# BMS_LOST_V1.net
KiCad netlist of a schematic drawn in Altium Designer
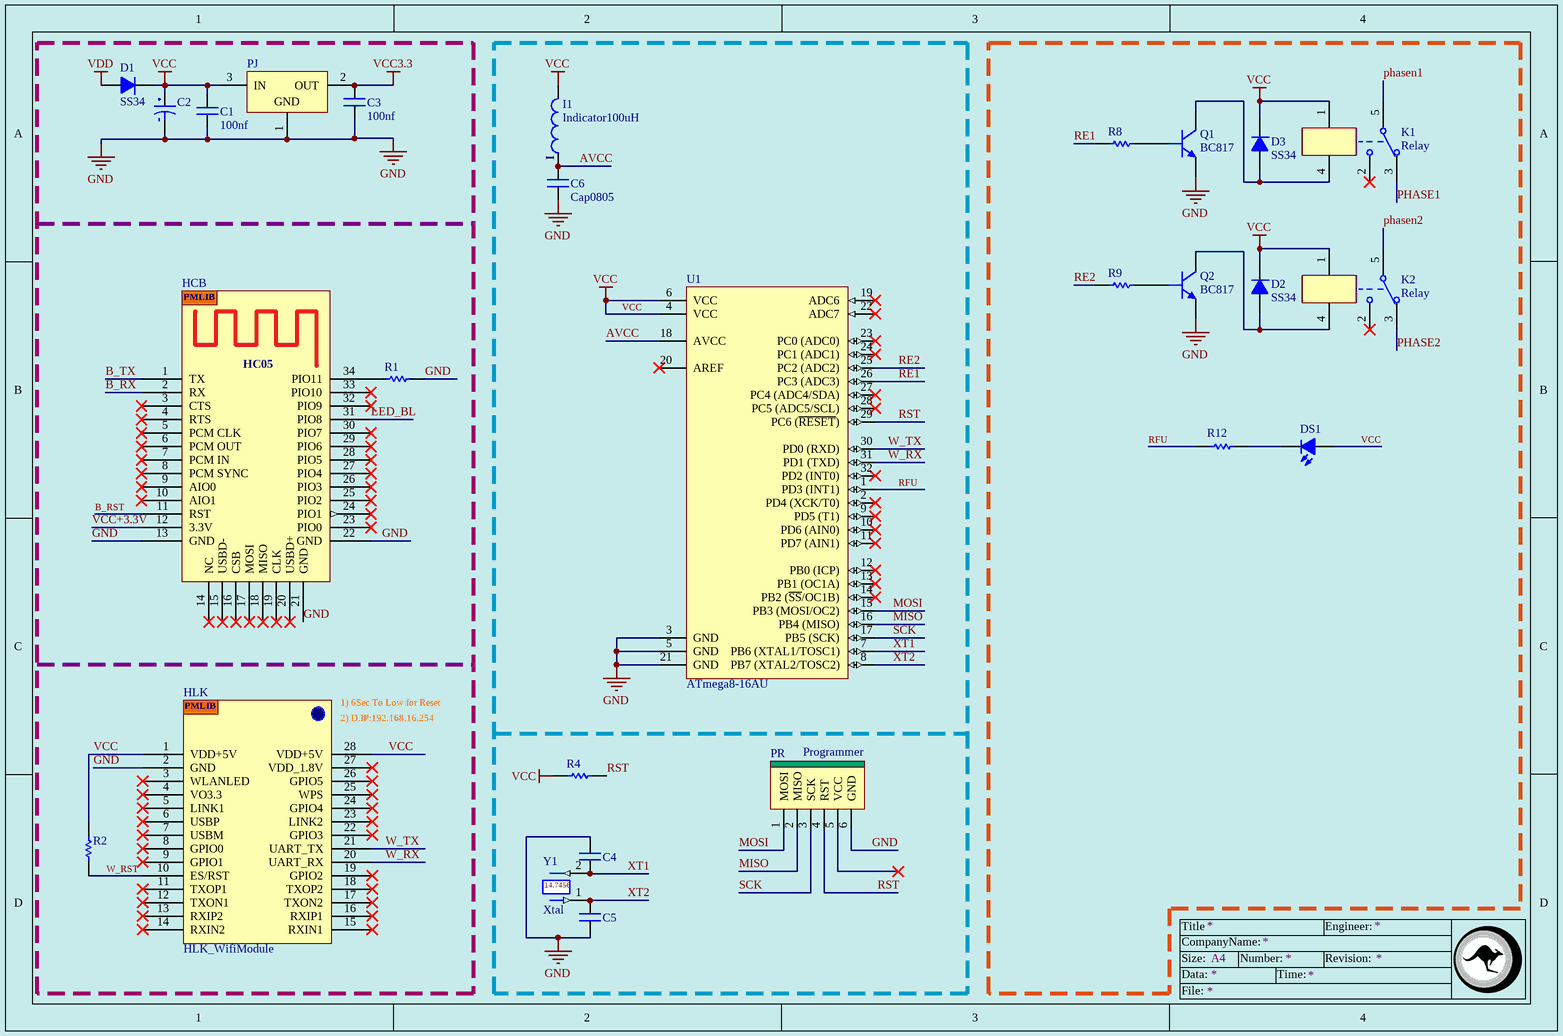
[diagram p0: BMS_LOST_V1.SchDoc]

(export (version "E")
  (design (tool "Eeschema 10.0.6"))
  (components
    (comp (ref "C1")
      (value "100nf")
      (footprint "Cap0805")
      (description "surface mount capacitor (size 805)")
      (libsource (lib "PMLIB") (part "Cap0805"))
    )
    (comp (ref "C2") (value "Cap_4mm") (footprint "2220") (libsource (lib "PMLIB") (part "Cap_Pola")))
    (comp (ref "C3")
      (value "100nf")
      (footprint "Cap0805")
      (description "surface mount capacitor (size 805)")
      (libsource (lib "PMLIB") (part "Cap0805"))
    )
    (comp (ref "C4")
      (value "CAP 805")
      (footprint "Cap0805")
      (description "surface mount capacitor (size 805)")
      (libsource (lib "PMLIB") (part "Cap0805"))
    )
    (comp (ref "C5")
      (value "CAP 805")
      (footprint "Cap0805")
      (description "surface mount capacitor (size 805)")
      (libsource (lib "PMLIB") (part "Cap0805"))
    )
    (comp (ref "C6")
      (value "Cap0805")
      (footprint "Cap0805")
      (description "surface mount capacitor (size 805)")
      (libsource (lib "PMLIB") (part "Cap0805"))
    )
    (comp (ref "D1") (value "SS34") (footprint "Diod-1A-SMD") (libsource (lib "PMLIB") (part "Diode")))
    (comp (ref "D2") (value "SS34") (footprint "Diod-1A-SMD") (libsource (lib "PMLIB") (part "Diode")))
    (comp (ref "D3") (value "SS34") (footprint "Diod-1A-SMD") (libsource (lib "PMLIB") (part "Diode")))
    (comp (ref "DS1") (value "LED1") (footprint "LED3MM") (libsource (lib "PMLIB") (part "LED1")))
    (comp (ref "HC")
      (value "HC05_Bluetooth")
      (footprint "HC05_Bluetooth")
      (libsource (lib "PMLIB") (part "HC05_Bluetooth"))
    )
    (comp (ref "HLK")
      (value "HLK_WifiModule")
      (footprint "HLK")
      (libsource (lib "PMLIB") (part "HLK_WifiModule"))
    )
    (comp (ref "I1")
      (value "Indicator100uH")
      (footprint "Indicator0805")
      (libsource (lib "PMLIB") (part "Indicator100uH"))
    )
    (comp (ref "K1")
      (value "Relay")
      (footprint "RelayMilionMiniS-Z")
      (libsource (lib "PMLIB") (part "RelayMilon"))
    )
    (comp (ref "K2")
      (value "Relay")
      (footprint "RelayMilionMiniS-Z")
      (libsource (lib "PMLIB") (part "RelayMilon"))
    )
    (comp (ref "PJ")
      (value "PJ1117_3.3V")
      (footprint "PJ1117s")
      (libsource (lib "PMLIB") (part "PJ1117_3.3V"))
    )
    (comp (ref "PR")
      (value "Programmer")
      (footprint "Programmer")
      (libsource (lib "PMLIB") (part "Programmer"))
    )
    (comp (ref "Q1") (value "BC817") (footprint "SOT23") (libsource (lib "PMLIB") (part "Transistor NPN")))
    (comp (ref "Q2") (value "BC817") (footprint "SOT23") (libsource (lib "PMLIB") (part "Transistor NPN")))
    (comp (ref "R1") (value "Res 0805") (footprint "R0805") (libsource (lib "PMLIB") (part "Res 0805")))
    (comp (ref "R2") (value "Res 0805") (footprint "R0805") (libsource (lib "PMLIB") (part "Res 0805")))
    (comp (ref "R4") (value "Res 0805") (footprint "R0805") (libsource (lib "PMLIB") (part "Res 0805")))
    (comp (ref "R8") (value "Res 0805") (footprint "R0805") (libsource (lib "PMLIB") (part "Res 0805")))
    (comp (ref "R9") (value "Res 0805") (footprint "R0805") (libsource (lib "PMLIB") (part "Res 0805")))
    (comp (ref "R12") (value "330") (footprint "R0805") (libsource (lib "PMLIB") (part "Res 0805")))
    (comp (ref "U1")
      (value "ATmega8-16AU")
      (footprint "32A_N")
      (libsource (lib "Atmel Microcontroller megaAVR") (part "ATmega8-16AU"))
    )
    (comp (ref "Y1") (value "Xtal") (footprint "CrystallB") (libsource (lib "PMLIB") (part "Crystal")))
  )
  (nets
    (net (code "1") (name "/AVCC") (class "Default")
      (node (ref "C6") (pin "2") (pinfunction "2_2") (pintype "passive"))
      (node (ref "I1") (pin "1") (pinfunction "1_1") (pintype "passive"))
      (node (ref "U1") (pin "18") (pinfunction "AVCC_18") (pintype "power_in"))
    )
    (net (code "2") (name "/B_RST") (class "Default")
      (node (ref "HC") (pin "11") (pinfunction "RST_11") (pintype "passive"))
    )
    (net (code "3") (name "/B_RX") (class "Default")
      (node (ref "HC") (pin "2") (pinfunction "RX_2") (pintype "passive"))
    )
    (net (code "4") (name "/B_TX") (class "Default")
      (node (ref "HC") (pin "1") (pinfunction "TX_1") (pintype "passive"))
    )
    (net (code "5") (name "/LED_BL") (class "Default")
      (node (ref "HC") (pin "31") (pinfunction "PIO8_31") (pintype "passive"))
    )
    (net (code "6") (name "/MISO") (class "Default")
      (node (ref "PR") (pin "2") (pinfunction "MISO_2") (pintype "passive"))
      (node (ref "U1") (pin "16") (pinfunction "PB4_(MISO)_16") (pintype "bidirectional"))
    )
    (net (code "7") (name "/MOSI") (class "Default")
      (node (ref "PR") (pin "1") (pinfunction "MOSI_1") (pintype "passive"))
      (node (ref "U1") (pin "15") (pinfunction "PB3_(MOSI/OC2)_15") (pintype "bidirectional"))
    )
    (net (code "8") (name "/PHASE1") (class "Default")
      (node (ref "K1") (pin "3") (pinfunction "3_3") (pintype "passive"))
    )
    (net (code "9") (name "/PHASE2") (class "Default")
      (node (ref "K2") (pin "3") (pinfunction "3_3") (pintype "passive"))
    )
    (net (code "10") (name "/RE1") (class "Default")
      (node (ref "R8") (pin "2") (pinfunction "2_2") (pintype "passive"))
      (node (ref "U1") (pin "26") (pinfunction "PC3_(ADC3)_26") (pintype "bidirectional"))
    )
    (net (code "11") (name "/RE2") (class "Default")
      (node (ref "R9") (pin "2") (pinfunction "2_2") (pintype "passive"))
      (node (ref "U1") (pin "25") (pinfunction "PC2_(ADC2)_25") (pintype "bidirectional"))
    )
    (net (code "12") (name "/RFU") (class "Default")
      (node (ref "R12") (pin "2") (pinfunction "2_2") (pintype "passive"))
      (node (ref "U1") (pin "1") (pinfunction "PD3_(INT1)_1") (pintype "bidirectional"))
    )
    (net (code "13") (name "/RST") (class "Default")
      (node (ref "PR") (pin "4") (pinfunction "RST_4") (pintype "passive"))
      (node (ref "R4") (pin "1") (pinfunction "1_1") (pintype "passive"))
      (node (ref "U1") (pin "29") (pinfunction "PC6_(~{RESET})_29") (pintype "bidirectional"))
    )
    (net (code "14") (name "/SCK") (class "Default")
      (node (ref "PR") (pin "3") (pinfunction "SCK_3") (pintype "passive"))
      (node (ref "U1") (pin "17") (pinfunction "PB5_(SCK)_17") (pintype "bidirectional"))
    )
    (net (code "15") (name "/VCC+3.3V") (class "Default")
      (node (ref "HC") (pin "12") (pinfunction "3.3V_12") (pintype "passive"))
    )
    (net (code "16") (name "/W_RST") (class "Default")
      (node (ref "HLK") (pin "10") (pinfunction "ES/RST_10") (pintype "passive"))
      (node (ref "R2") (pin "2") (pinfunction "2_2") (pintype "passive"))
    )
    (net (code "17") (name "/W_RX") (class "Default")
      (node (ref "HLK") (pin "20") (pinfunction "UART_RX_20") (pintype "passive"))
      (node (ref "U1") (pin "31") (pinfunction "PD1_(TXD)_31") (pintype "bidirectional"))
    )
    (net (code "18") (name "/W_TX") (class "Default")
      (node (ref "HLK") (pin "21") (pinfunction "UART_TX_21") (pintype "passive"))
      (node (ref "U1") (pin "30") (pinfunction "PD0_(RXD)_30") (pintype "bidirectional"))
    )
    (net (code "19") (name "/XT1") (class "Default")
      (node (ref "C4") (pin "1") (pinfunction "1_1") (pintype "passive"))
      (node (ref "U1") (pin "7") (pinfunction "PB6_(XTAL1/TOSC1)_7") (pintype "bidirectional"))
      (node (ref "Y1") (pin "2") (pinfunction "2_2") (pintype "input"))
    )
    (net (code "20") (name "/XT2") (class "Default")
      (node (ref "C5") (pin "2") (pinfunction "2_2") (pintype "passive"))
      (node (ref "U1") (pin "8") (pinfunction "PB7_(XTAL2/TOSC2)_8") (pintype "bidirectional"))
      (node (ref "Y1") (pin "1") (pinfunction "1_1") (pintype "output"))
    )
    (net (code "21") (name "/phasen1") (class "Default")
      (node (ref "K1") (pin "5") (pinfunction "5_5") (pintype "passive"))
    )
    (net (code "22") (name "/phasen2") (class "Default")
      (node (ref "K2") (pin "5") (pinfunction "5_5") (pintype "passive"))
    )
    (net (code "23") (name "GND") (class "Default")
      (node (ref "C1") (pin "2") (pinfunction "2_2") (pintype "passive"))
      (node (ref "C2") (pin "1") (pinfunction "1_1") (pintype "passive"))
      (node (ref "C3") (pin "2") (pinfunction "2_2") (pintype "passive"))
      (node (ref "C4") (pin "2") (pinfunction "2_2") (pintype "passive"))
      (node (ref "C5") (pin "1") (pinfunction "1_1") (pintype "passive"))
      (node (ref "C6") (pin "1") (pinfunction "1_1") (pintype "passive"))
      (node (ref "HC") (pin "13") (pinfunction "GND_13") (pintype "power_in"))
      (node (ref "HC") (pin "21") (pinfunction "GND_21") (pintype "passive"))
      (node (ref "HC") (pin "22") (pinfunction "GND_22") (pintype "passive"))
      (node (ref "HLK") (pin "2") (pinfunction "GND_2") (pintype "passive"))
      (node (ref "PJ") (pin "1") (pinfunction "GND_1") (pintype "power_in"))
      (node (ref "PR") (pin "6") (pinfunction "GND_6") (pintype "passive"))
      (node (ref "Q1") (pin "2") (pinfunction "E_2") (pintype "passive"))
      (node (ref "Q2") (pin "2") (pinfunction "E_2") (pintype "passive"))
      (node (ref "R1") (pin "1") (pinfunction "1_1") (pintype "passive"))
      (node (ref "U1") (pin "21") (pinfunction "GND_21") (pintype "power_in"))
      (node (ref "U1") (pin "3") (pinfunction "GND_3") (pintype "power_in"))
      (node (ref "U1") (pin "5") (pinfunction "GND_5") (pintype "power_in"))
    )
    (net (code "24") (name "Net-(DS1-PadK)") (class "Default")
      (node (ref "DS1") (pin "K") (pinfunction "K_K") (pintype "passive"))
      (node (ref "R12") (pin "1") (pinfunction "1_1") (pintype "passive"))
    )
    (net (code "25") (name "Net-(HCB-PIO11)") (class "Default")
      (node (ref "HC") (pin "34") (pinfunction "PIO11_34") (pintype "passive"))
      (node (ref "R1") (pin "2") (pinfunction "2_2") (pintype "passive"))
    )
    (net (code "26") (name "Net-(Q1-B)") (class "Default")
      (node (ref "Q1") (pin "1") (pinfunction "B_1") (pintype "passive"))
      (node (ref "R8") (pin "1") (pinfunction "1_1") (pintype "passive"))
    )
    (net (code "27") (name "Net-(Q1-C)") (class "Default")
      (node (ref "D3") (pin "A") (pinfunction "A_A") (pintype "passive"))
      (node (ref "K1") (pin "4") (pinfunction "4_4") (pintype "passive"))
      (node (ref "Q1") (pin "3") (pinfunction "C_3") (pintype "passive"))
    )
    (net (code "28") (name "Net-(Q2-B)") (class "Default")
      (node (ref "Q2") (pin "1") (pinfunction "B_1") (pintype "passive"))
      (node (ref "R9") (pin "1") (pinfunction "1_1") (pintype "passive"))
    )
    (net (code "29") (name "Net-(Q2-C)") (class "Default")
      (node (ref "D2") (pin "A") (pinfunction "A_A") (pintype "passive"))
      (node (ref "K2") (pin "4") (pinfunction "4_4") (pintype "passive"))
      (node (ref "Q2") (pin "3") (pinfunction "C_3") (pintype "passive"))
    )
    (net (code "30") (name "VCC") (class "Default")
      (node (ref "C1") (pin "1") (pinfunction "1_1") (pintype "passive"))
      (node (ref "C2") (pin "2") (pinfunction "2_2") (pintype "passive"))
      (node (ref "D1") (pin "K") (pinfunction "K_K") (pintype "passive"))
      (node (ref "D2") (pin "K") (pinfunction "K_K") (pintype "passive"))
      (node (ref "D3") (pin "K") (pinfunction "K_K") (pintype "passive"))
      (node (ref "DS1") (pin "A") (pinfunction "A_A") (pintype "passive"))
      (node (ref "HLK") (pin "1") (pinfunction "VDD+5V_1") (pintype "passive"))
      (node (ref "HLK") (pin "28") (pinfunction "VDD+5V_28") (pintype "passive"))
      (node (ref "I1") (pin "2") (pinfunction "2_2") (pintype "passive"))
      (node (ref "K1") (pin "1") (pinfunction "1_1") (pintype "passive"))
      (node (ref "K2") (pin "1") (pinfunction "1_1") (pintype "passive"))
      (node (ref "PJ") (pin "3") (pinfunction "IN_3") (pintype "power_in"))
      (node (ref "R2") (pin "1") (pinfunction "1_1") (pintype "passive"))
      (node (ref "R4") (pin "2") (pinfunction "2_2") (pintype "passive"))
      (node (ref "U1") (pin "4") (pinfunction "VCC_4") (pintype "power_in"))
      (node (ref "U1") (pin "6") (pinfunction "VCC_6") (pintype "power_in"))
    )
    (net (code "31") (name "VCC3.3") (class "Default")
      (node (ref "C3") (pin "1") (pinfunction "1_1") (pintype "passive"))
      (node (ref "PJ") (pin "2") (pinfunction "OUT_2") (pintype "power_in"))
    )
    (net (code "32") (name "VDD") (class "Default")
      (node (ref "D1") (pin "A") (pinfunction "A_A") (pintype "passive"))
    )
    (net (code "33") (name "unconnected-(HCB-AIO0-Pad9)") (class "Default")
      (node (ref "HC") (pin "9") (pinfunction "AIO0_9") (pintype "passive+no_connect"))
    )
    (net (code "34") (name "unconnected-(HCB-AIO1-Pad10)") (class "Default")
      (node (ref "HC") (pin "10") (pinfunction "AIO1_10") (pintype "passive+no_connect"))
    )
    (net (code "35") (name "unconnected-(HCB-CLK-Pad19)") (class "Default")
      (node (ref "HC") (pin "19") (pinfunction "CLK_19") (pintype "passive+no_connect"))
    )
    (net (code "36") (name "unconnected-(HCB-CSB-Pad16)") (class "Default")
      (node (ref "HC") (pin "16") (pinfunction "CSB_16") (pintype "passive+no_connect"))
    )
    (net (code "37") (name "unconnected-(HCB-CTS-Pad3)") (class "Default")
      (node (ref "HC") (pin "3") (pinfunction "CTS_3") (pintype "passive+no_connect"))
    )
    (net (code "38") (name "unconnected-(HCB-MISO-Pad18)") (class "Default")
      (node (ref "HC") (pin "18") (pinfunction "MISO_18") (pintype "passive+no_connect"))
    )
    (net (code "39") (name "unconnected-(HCB-MOSI-Pad17)") (class "Default")
      (node (ref "HC") (pin "17") (pinfunction "MOSI_17") (pintype "passive+no_connect"))
    )
    (net (code "40") (name "unconnected-(HCB-NC-Pad14)") (class "Default")
      (node (ref "HC") (pin "14") (pinfunction "NC_14") (pintype "passive+no_connect"))
    )
    (net (code "41") (name "unconnected-(HCB-PCM_CLK-Pad5)") (class "Default")
      (node (ref "HC") (pin "5") (pinfunction "PCM_CLK_5") (pintype "passive+no_connect"))
    )
    (net (code "42") (name "unconnected-(HCB-PCM_IN-Pad7)") (class "Default")
      (node (ref "HC") (pin "7") (pinfunction "PCM_IN_7") (pintype "passive+no_connect"))
    )
    (net (code "43") (name "unconnected-(HCB-PCM_OUT-Pad6)") (class "Default")
      (node (ref "HC") (pin "6") (pinfunction "PCM_OUT_6") (pintype "passive+no_connect"))
    )
    (net (code "44") (name "unconnected-(HCB-PCM_SYNC-Pad8)") (class "Default")
      (node (ref "HC") (pin "8") (pinfunction "PCM_SYNC_8") (pintype "passive+no_connect"))
    )
    (net (code "45") (name "unconnected-(HCB-PIO0-Pad23)") (class "Default")
      (node (ref "HC") (pin "23") (pinfunction "PIO0_23") (pintype "passive+no_connect"))
    )
    (net (code "46") (name "unconnected-(HCB-PIO1-Pad24)") (class "Default")
      (node (ref "HC") (pin "24") (pinfunction "PIO1_24") (pintype "output+no_connect"))
    )
    (net (code "47") (name "unconnected-(HCB-PIO2-Pad25)") (class "Default")
      (node (ref "HC") (pin "25") (pinfunction "PIO2_25") (pintype "passive+no_connect"))
    )
    (net (code "48") (name "unconnected-(HCB-PIO3-Pad26)") (class "Default")
      (node (ref "HC") (pin "26") (pinfunction "PIO3_26") (pintype "passive+no_connect"))
    )
    (net (code "49") (name "unconnected-(HCB-PIO4-Pad27)") (class "Default")
      (node (ref "HC") (pin "27") (pinfunction "PIO4_27") (pintype "passive+no_connect"))
    )
    (net (code "50") (name "unconnected-(HCB-PIO5-Pad28)") (class "Default")
      (node (ref "HC") (pin "28") (pinfunction "PIO5_28") (pintype "passive+no_connect"))
    )
    (net (code "51") (name "unconnected-(HCB-PIO6-Pad29)") (class "Default")
      (node (ref "HC") (pin "29") (pinfunction "PIO6_29") (pintype "passive+no_connect"))
    )
    (net (code "52") (name "unconnected-(HCB-PIO7-Pad30)") (class "Default")
      (node (ref "HC") (pin "30") (pinfunction "PIO7_30") (pintype "passive+no_connect"))
    )
    (net (code "53") (name "unconnected-(HCB-PIO9-Pad32)") (class "Default")
      (node (ref "HC") (pin "32") (pinfunction "PIO9_32") (pintype "passive+no_connect"))
    )
    (net (code "54") (name "unconnected-(HCB-PIO10-Pad33)") (class "Default")
      (node (ref "HC") (pin "33") (pinfunction "PIO10_33") (pintype "passive+no_connect"))
    )
    (net (code "55") (name "unconnected-(HCB-RTS-Pad4)") (class "Default")
      (node (ref "HC") (pin "4") (pinfunction "RTS_4") (pintype "passive+no_connect"))
    )
    (net (code "56") (name "unconnected-(HCB-USBD+-Pad20)") (class "Default")
      (node (ref "HC") (pin "20") (pinfunction "USBD+_20") (pintype "passive+no_connect"))
    )
    (net (code "57") (name "unconnected-(HCB-USBD--Pad15)") (class "Default")
      (node (ref "HC") (pin "15") (pinfunction "USBD-_15") (pintype "passive+no_connect"))
    )
    (net (code "58") (name "unconnected-(HLK-GPIO0-Pad8)") (class "Default")
      (node (ref "HLK") (pin "8") (pinfunction "GPIO0_8") (pintype "passive+no_connect"))
    )
    (net (code "59") (name "unconnected-(HLK-GPIO1-Pad9)") (class "Default")
      (node (ref "HLK") (pin "9") (pinfunction "GPIO1_9") (pintype "passive+no_connect"))
    )
    (net (code "60") (name "unconnected-(HLK-GPIO2-Pad19)") (class "Default")
      (node (ref "HLK") (pin "19") (pinfunction "GPIO2_19") (pintype "passive+no_connect"))
    )
    (net (code "61") (name "unconnected-(HLK-GPIO3-Pad22)") (class "Default")
      (node (ref "HLK") (pin "22") (pinfunction "GPIO3_22") (pintype "passive+no_connect"))
    )
    (net (code "62") (name "unconnected-(HLK-GPIO4-Pad24)") (class "Default")
      (node (ref "HLK") (pin "24") (pinfunction "GPIO4_24") (pintype "passive+no_connect"))
    )
    (net (code "63") (name "unconnected-(HLK-GPIO5-Pad26)") (class "Default")
      (node (ref "HLK") (pin "26") (pinfunction "GPIO5_26") (pintype "passive+no_connect"))
    )
    (net (code "64") (name "unconnected-(HLK-LINK1-Pad5)") (class "Default")
      (node (ref "HLK") (pin "5") (pinfunction "LINK1_5") (pintype "passive+no_connect"))
    )
    (net (code "65") (name "unconnected-(HLK-LINK2-Pad23)") (class "Default")
      (node (ref "HLK") (pin "23") (pinfunction "LINK2_23") (pintype "passive+no_connect"))
    )
    (net (code "66") (name "unconnected-(HLK-RXIN1-Pad15)") (class "Default")
      (node (ref "HLK") (pin "15") (pinfunction "RXIN1_15") (pintype "passive+no_connect"))
    )
    (net (code "67") (name "unconnected-(HLK-RXIN2-Pad14)") (class "Default")
      (node (ref "HLK") (pin "14") (pinfunction "RXIN2_14") (pintype "passive+no_connect"))
    )
    (net (code "68") (name "unconnected-(HLK-RXIP1-Pad16)") (class "Default")
      (node (ref "HLK") (pin "16") (pinfunction "RXIP1_16") (pintype "passive+no_connect"))
    )
    (net (code "69") (name "unconnected-(HLK-RXIP2-Pad13)") (class "Default")
      (node (ref "HLK") (pin "13") (pinfunction "RXIP2_13") (pintype "passive+no_connect"))
    )
    (net (code "70") (name "unconnected-(HLK-TXON1-Pad12)") (class "Default")
      (node (ref "HLK") (pin "12") (pinfunction "TXON1_12") (pintype "passive+no_connect"))
    )
    (net (code "71") (name "unconnected-(HLK-TXON2-Pad17)") (class "Default")
      (node (ref "HLK") (pin "17") (pinfunction "TXON2_17") (pintype "passive+no_connect"))
    )
    (net (code "72") (name "unconnected-(HLK-TXOP1-Pad11)") (class "Default")
      (node (ref "HLK") (pin "11") (pinfunction "TXOP1_11") (pintype "passive+no_connect"))
    )
    (net (code "73") (name "unconnected-(HLK-TXOP2-Pad18)") (class "Default")
      (node (ref "HLK") (pin "18") (pinfunction "TXOP2_18") (pintype "passive+no_connect"))
    )
    (net (code "74") (name "unconnected-(HLK-USBM-Pad7)") (class "Default")
      (node (ref "HLK") (pin "7") (pinfunction "USBM_7") (pintype "passive+no_connect"))
    )
    (net (code "75") (name "unconnected-(HLK-USBP-Pad6)") (class "Default")
      (node (ref "HLK") (pin "6") (pinfunction "USBP_6") (pintype "passive+no_connect"))
    )
    (net (code "76") (name "unconnected-(HLK-VDD_1.8V-Pad27)") (class "Default")
      (node (ref "HLK") (pin "27") (pinfunction "VDD_1.8V_27") (pintype "passive+no_connect"))
    )
    (net (code "77") (name "unconnected-(HLK-VO3.3-Pad4)") (class "Default")
      (node (ref "HLK") (pin "4") (pinfunction "VO3.3_4") (pintype "passive+no_connect"))
    )
    (net (code "78") (name "unconnected-(HLK-WLANLED-Pad3)") (class "Default")
      (node (ref "HLK") (pin "3") (pinfunction "WLANLED_3") (pintype "passive+no_connect"))
    )
    (net (code "79") (name "unconnected-(HLK-WPS-Pad25)") (class "Default")
      (node (ref "HLK") (pin "25") (pinfunction "WPS_25") (pintype "passive+no_connect"))
    )
    (net (code "80") (name "unconnected-(K1-Pad2)") (class "Default")
      (node (ref "K1") (pin "2") (pinfunction "2_2") (pintype "passive+no_connect"))
    )
    (net (code "81") (name "unconnected-(K2-Pad2)") (class "Default")
      (node (ref "K2") (pin "2") (pinfunction "2_2") (pintype "passive+no_connect"))
    )
    (net (code "82") (name "unconnected-(PR-VCC-Pad5)") (class "Default")
      (node (ref "PR") (pin "5") (pinfunction "VCC_5") (pintype "passive+no_connect"))
    )
    (net (code "83") (name "unconnected-(U1-ADC6-Pad19)") (class "Default")
      (node (ref "U1") (pin "19") (pinfunction "ADC6_19") (pintype "input+no_connect"))
    )
    (net (code "84") (name "unconnected-(U1-ADC7-Pad22)") (class "Default")
      (node (ref "U1") (pin "22") (pinfunction "ADC7_22") (pintype "input+no_connect"))
    )
    (net (code "85") (name "unconnected-(U1-AREF-Pad20)") (class "Default")
      (node (ref "U1") (pin "20") (pinfunction "AREF_20") (pintype "passive+no_connect"))
    )
    (net (code "86") (name "unconnected-(U1-PB0_(ICP)-Pad12)") (class "Default")
      (node (ref "U1") (pin "12") (pinfunction "PB0_(ICP)_12") (pintype "bidirectional+no_connect"))
    )
    (net (code "87") (name "unconnected-(U1-PB1_(OC1A)-Pad13)") (class "Default")
      (node (ref "U1") (pin "13") (pinfunction "PB1_(OC1A)_13") (pintype "bidirectional+no_connect"))
    )
    (net (code "88") (name "unconnected-(U1-PB2_(~{SS}{slash}OC1B)-Pad14)") (class "Default")
      (node (ref "U1") (pin "14") (pinfunction "PB2_(~{SS}/OC1B)_14") (pintype "bidirectional+no_connect"))
    )
    (net (code "89") (name "unconnected-(U1-PC0_(ADC0)-Pad23)") (class "Default")
      (node (ref "U1") (pin "23") (pinfunction "PC0_(ADC0)_23") (pintype "bidirectional+no_connect"))
    )
    (net (code "90") (name "unconnected-(U1-PC1_(ADC1)-Pad24)") (class "Default")
      (node (ref "U1") (pin "24") (pinfunction "PC1_(ADC1)_24") (pintype "bidirectional+no_connect"))
    )
    (net (code "91") (name "unconnected-(U1-PC4_(ADC4{slash}SDA)-Pad27)") (class "Default")
      (node (ref "U1") (pin "27") (pinfunction "PC4_(ADC4/SDA)_27") (pintype "bidirectional+no_connect"))
    )
    (net (code "92") (name "unconnected-(U1-PC5_(ADC5{slash}SCL)-Pad28)") (class "Default")
      (node (ref "U1") (pin "28") (pinfunction "PC5_(ADC5/SCL)_28") (pintype "bidirectional+no_connect"))
    )
    (net (code "93") (name "unconnected-(U1-PD2_(INT0)-Pad32)") (class "Default")
      (node (ref "U1") (pin "32") (pinfunction "PD2_(INT0)_32") (pintype "bidirectional+no_connect"))
    )
    (net (code "94") (name "unconnected-(U1-PD4_(XCK{slash}T0)-Pad2)") (class "Default")
      (node (ref "U1") (pin "2") (pinfunction "PD4_(XCK/T0)_2") (pintype "bidirectional+no_connect"))
    )
    (net (code "95") (name "unconnected-(U1-PD5_(T1)-Pad9)") (class "Default")
      (node (ref "U1") (pin "9") (pinfunction "PD5_(T1)_9") (pintype "bidirectional+no_connect"))
    )
    (net (code "96") (name "unconnected-(U1-PD6_(AIN0)-Pad10)") (class "Default")
      (node (ref "U1") (pin "10") (pinfunction "PD6_(AIN0)_10") (pintype "bidirectional+no_connect"))
    )
    (net (code "97") (name "unconnected-(U1-PD7_(AIN1)-Pad11)") (class "Default")
      (node (ref "U1") (pin "11") (pinfunction "PD7_(AIN1)_11") (pintype "bidirectional+no_connect"))
    )
  )
)
